# shiftRegister.net
KiCad netlist of a schematic drawn in Altium Designer
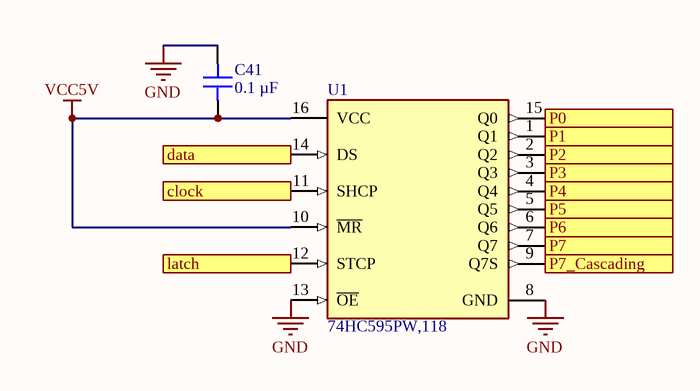
[diagram p0: shiftRegister.SchDoc]

(export (version "E")
  (design (tool "Eeschema 10.0.6"))
  (components
    (comp (ref "C41")
      (value "0.1 µF")
      (footprint "CAP 0603_1608")
      (description "CAP CER 0.1UF 50V X7R 0603")
      (fields (field (name "PART NUMBER") "C0603C104K5RAC7411") (field (name "MANUFACTURER") "KEMET"))
      (libsource (lib "Celestial Altium Library - altium_library") (part "Capacitor"))
    )
    (comp (ref "U1")
      (value "74HC595PW,118")
      (footprint "FP-SOT403-1-MFG")
      (description "IC SHIFT REGISTER 8BIT 16TSSOP")
      (libsource (lib "Altium Content Vault") (part "27683e23285b137cd268a0f18c66bed"))
    )
  )
  (nets
    (net (code "1") (name "/P0") (class "Default")
      (node (ref "U1") (pin "15") (pinfunction "Q0_15") (pintype "output"))
    )
    (net (code "2") (name "/P1") (class "Default")
      (node (ref "U1") (pin "1") (pinfunction "Q1_1") (pintype "output"))
    )
    (net (code "3") (name "/P2") (class "Default")
      (node (ref "U1") (pin "2") (pinfunction "Q2_2") (pintype "output"))
    )
    (net (code "4") (name "/P3") (class "Default")
      (node (ref "U1") (pin "3") (pinfunction "Q3_3") (pintype "output"))
    )
    (net (code "5") (name "/P4") (class "Default")
      (node (ref "U1") (pin "4") (pinfunction "Q4_4") (pintype "output"))
    )
    (net (code "6") (name "/P5") (class "Default")
      (node (ref "U1") (pin "5") (pinfunction "Q5_5") (pintype "output"))
    )
    (net (code "7") (name "/P6") (class "Default")
      (node (ref "U1") (pin "6") (pinfunction "Q6_6") (pintype "output"))
    )
    (net (code "8") (name "/P7") (class "Default")
      (node (ref "U1") (pin "7") (pinfunction "Q7_7") (pintype "output"))
    )
    (net (code "9") (name "/P7_Cascading") (class "Default")
      (node (ref "U1") (pin "9") (pinfunction "Q7S_9") (pintype "output"))
    )
    (net (code "10") (name "/clock") (class "Default")
      (node (ref "U1") (pin "11") (pinfunction "SHCP_11") (pintype "input"))
    )
    (net (code "11") (name "/data") (class "Default")
      (node (ref "U1") (pin "14") (pinfunction "DS_14") (pintype "input"))
    )
    (net (code "12") (name "/latch") (class "Default")
      (node (ref "U1") (pin "12") (pinfunction "STCP_12") (pintype "input"))
    )
    (net (code "13") (name "GND") (class "Default")
      (node (ref "C41") (pin "2") (pinfunction "2_2") (pintype "passive"))
      (node (ref "U1") (pin "13") (pinfunction "~{OE}_13") (pintype "input"))
      (node (ref "U1") (pin "8") (pinfunction "GND_8") (pintype "power_in"))
    )
    (net (code "14") (name "VCC5V") (class "Default")
      (node (ref "C41") (pin "1") (pinfunction "1_1") (pintype "passive"))
      (node (ref "U1") (pin "10") (pinfunction "~{MR}_10") (pintype "input"))
      (node (ref "U1") (pin "16") (pinfunction "VCC_16") (pintype "power_in"))
    )
  )
)
